# serlcd841.net
KiCad netlist of a schematic drawn in EAGLE
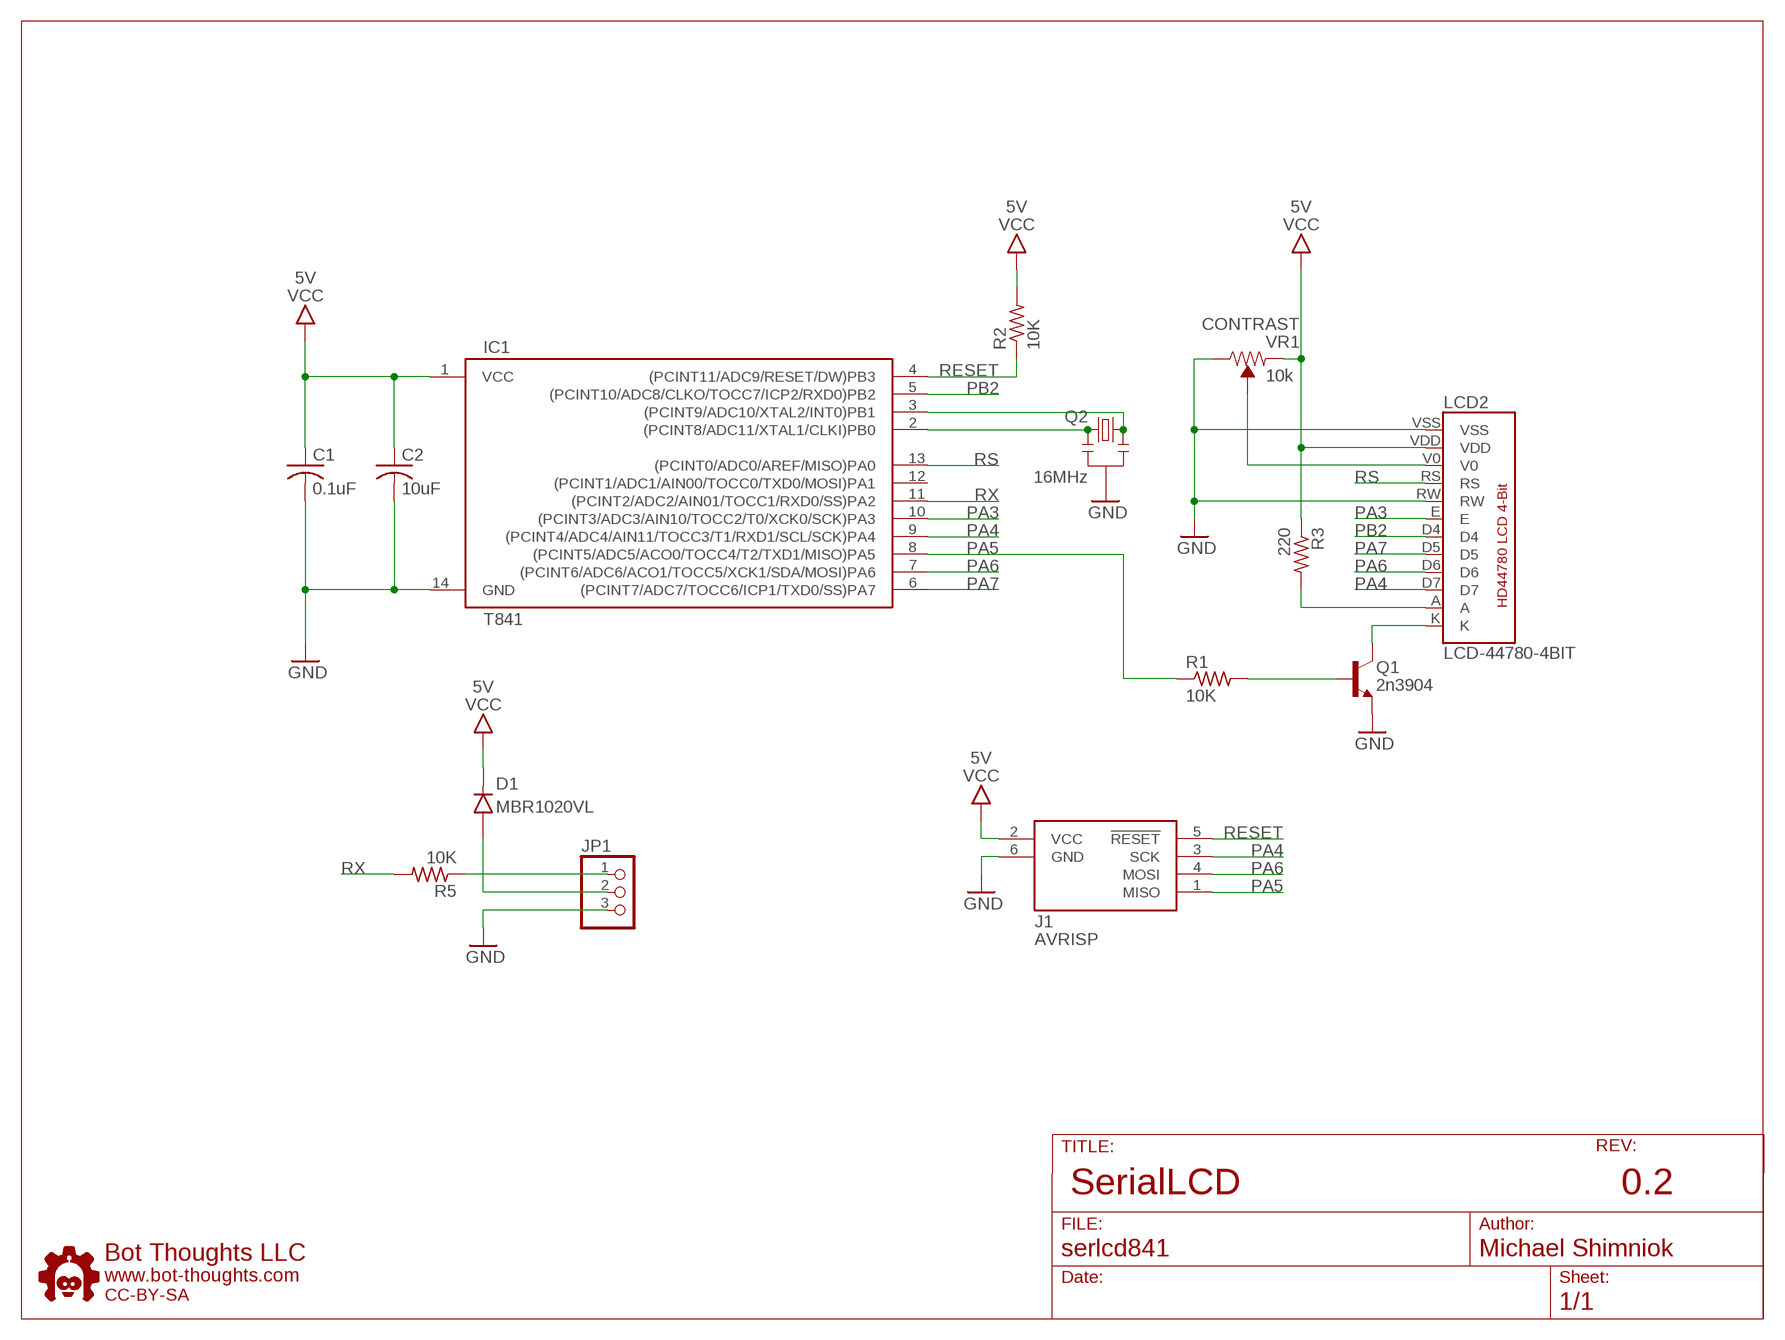
[diagram p0: schematic, sheet 1]

(export (version "E")
  (design (tool "Eeschema 10.0.6"))
  (components
    (comp (ref "C1")
      (value "0.1uF")
      (footprint "eagle-import:0603")
      (libsource (lib "eagle-import") (part "C-0603"))
    )
    (comp (ref "C2")
      (value "10uF")
      (footprint "eagle-import:1206")
      (libsource (lib "eagle-import") (part "C-1206"))
    )
    (comp (ref "D1")
      (value "MBR1020VL")
      (footprint "eagle-import:SOD123FL")
      (libsource (lib "eagle-import") (part "DIODE_SOD123FL"))
    )
    (comp (ref "IC1")
      (value "T841")
      (footprint "eagle-import:SOIC14N")
      (libsource (lib "eagle-import") (part "ATTINY441/841-SSU"))
    )
    (comp (ref "J1")
      (value "AVRISP")
      (footprint "eagle-import:CON6P2R")
      (libsource (lib "eagle-import") (part "AVRISP6_COMPACT"))
    )
    (comp (ref "JP1")
      (value "PINHD-1X03_2.54-S")
      (footprint "eagle-import:1X03-S")
      (libsource (lib "eagle-import") (part "PINHD-1X03_2.54-S"))
    )
    (comp (ref "LCD2")
      (value "LCD-44780-4BIT")
      (footprint "eagle-import:LCD16SIP")
      (libsource (lib "eagle-import") (part "LCD-44780-4BIT"))
    )
    (comp (ref "Q1")
      (value "2n3904")
      (footprint "eagle-import:SOT-23")
      (libsource (lib "eagle-import") (part "BJT-NPNSOT23"))
    )
    (comp (ref "Q2")
      (value "16MHz")
      (footprint "eagle-import:CSTCE_V_C")
      (libsource (lib "eagle-import") (part "RESONATOR_CSTCE_V_C"))
    )
    (comp (ref "R1")
      (value "10K")
      (footprint "eagle-import:0603")
      (libsource (lib "eagle-import") (part "R0603"))
    )
    (comp (ref "R2")
      (value "10K")
      (footprint "eagle-import:0603")
      (libsource (lib "eagle-import") (part "R0603"))
    )
    (comp (ref "R3")
      (value "220")
      (footprint "eagle-import:0603")
      (libsource (lib "eagle-import") (part "R0603"))
    )
    (comp (ref "R5")
      (value "10K")
      (footprint "eagle-import:0603")
      (libsource (lib "eagle-import") (part "R0603"))
    )
    (comp (ref "U$6")
      (value "BTLOGO-LOGO-MD")
      (footprint "eagle-import:BTLOGOM")
      (libsource (lib "eagle-import") (part "BTLOGO-LOGO-MD"))
    )
    (comp (ref "VR1")
      (value "10k")
      (footprint "eagle-import:TRIMPOT-SMD-TC33X")
      (libsource (lib "eagle-import") (part "TRIMPOT-SMD-3MM-OPEN-1/10W-25%"))
    )
  )
  (nets
    (net (code "1") (name "/PA3") (class "Default")
      (node (ref "IC1") (pin "10") (pinfunction "(PCINT3/ADC3/AIN10/TOCC2/T0/XCK0/SCK)PA3_10") (pintype "bidirectional"))
      (node (ref "LCD2") (pin "E") (pinfunction "E_E") (pintype "bidirectional"))
    )
    (net (code "2") (name "/PA4") (class "Default")
      (node (ref "IC1") (pin "9") (pinfunction "(PCINT4/ADC4/AIN11/TOCC3/T1/RXD1/SCL/SCK)PA4_9") (pintype "bidirectional"))
      (node (ref "J1") (pin "3") (pinfunction "SCK_3") (pintype "output"))
      (node (ref "LCD2") (pin "D7") (pinfunction "D7_D7") (pintype "bidirectional"))
    )
    (net (code "3") (name "/PA5") (class "Default")
      (node (ref "IC1") (pin "8") (pinfunction "(PCINT5/ADC5/ACO0/TOCC4/T2/TXD1/MISO)PA5_8") (pintype "bidirectional"))
      (node (ref "J1") (pin "1") (pinfunction "MISO_1") (pintype "input"))
      (node (ref "R1") (pin "1") (pinfunction "1_1") (pintype "passive"))
    )
    (net (code "4") (name "/PA6") (class "Default")
      (node (ref "IC1") (pin "7") (pinfunction "(PCINT6/ADC6/ACO1/TOCC5/XCK1/SDA/MOSI)PA6_7") (pintype "bidirectional"))
      (node (ref "J1") (pin "4") (pinfunction "MOSI_4") (pintype "output"))
      (node (ref "LCD2") (pin "D6") (pinfunction "D6_D6") (pintype "bidirectional"))
    )
    (net (code "5") (name "/PA7") (class "Default")
      (node (ref "IC1") (pin "6") (pinfunction "(PCINT7/ADC7/TOCC6/ICP1/TXD0/SS)PA7_6") (pintype "bidirectional"))
      (node (ref "LCD2") (pin "D5") (pinfunction "D5_D5") (pintype "bidirectional"))
    )
    (net (code "6") (name "/PB2") (class "Default")
      (node (ref "IC1") (pin "5") (pinfunction "(PCINT10/ADC8/CLKO/TOCC7/ICP2/RXD0)PB2_5") (pintype "bidirectional"))
      (node (ref "LCD2") (pin "D4") (pinfunction "D4_D4") (pintype "bidirectional"))
    )
    (net (code "7") (name "/RESET") (class "Default")
      (node (ref "IC1") (pin "4") (pinfunction "(PCINT11/ADC9/RESET/DW)PB3_4") (pintype "bidirectional"))
      (node (ref "J1") (pin "5") (pinfunction "~{RESET}_5") (pintype "output"))
      (node (ref "R2") (pin "1") (pinfunction "1_1") (pintype "passive"))
    )
    (net (code "8") (name "/RS") (class "Default")
      (node (ref "IC1") (pin "13") (pinfunction "(PCINT0/ADC0/AREF/MISO)PA0_13") (pintype "bidirectional"))
      (node (ref "LCD2") (pin "RS") (pinfunction "RS_RS") (pintype "bidirectional"))
    )
    (net (code "9") (name "/RX") (class "Default")
      (node (ref "IC1") (pin "11") (pinfunction "(PCINT2/ADC2/AIN01/TOCC1/RXD0/SS)PA2_11") (pintype "bidirectional"))
      (node (ref "R5") (pin "2") (pinfunction "2_2") (pintype "passive"))
    )
    (net (code "10") (name "5V") (class "Default")
      (node (ref "C1") (pin "1") (pinfunction "+_1") (pintype "passive"))
      (node (ref "C2") (pin "1") (pinfunction "+_1") (pintype "passive"))
      (node (ref "D1") (pin "C") (pinfunction "C_C") (pintype "passive"))
      (node (ref "IC1") (pin "1") (pinfunction "VCC_1") (pintype "bidirectional"))
      (node (ref "J1") (pin "2") (pinfunction "VCC_2") (pintype "power_in"))
      (node (ref "LCD2") (pin "VDD") (pinfunction "VDD_VDD") (pintype "bidirectional"))
      (node (ref "R2") (pin "2") (pinfunction "2_2") (pintype "passive"))
      (node (ref "R3") (pin "1") (pinfunction "1_1") (pintype "passive"))
      (node (ref "VR1") (pin "3") (pinfunction "CCW_3") (pintype "passive"))
    )
    (net (code "11") (name "GND") (class "Default")
      (node (ref "C1") (pin "2") (pinfunction "-_2") (pintype "passive"))
      (node (ref "C2") (pin "2") (pinfunction "-_2") (pintype "passive"))
      (node (ref "IC1") (pin "14") (pinfunction "GND_14") (pintype "bidirectional"))
      (node (ref "J1") (pin "6") (pinfunction "GND_6") (pintype "power_in"))
      (node (ref "JP1") (pin "3") (pinfunction "3_3") (pintype "passive"))
      (node (ref "LCD2") (pin "RW") (pinfunction "RW_RW") (pintype "bidirectional"))
      (node (ref "LCD2") (pin "VSS") (pinfunction "VSS_VSS") (pintype "bidirectional"))
      (node (ref "Q1") (pin "2") (pinfunction "E_2") (pintype "passive"))
      (node (ref "Q2") (pin "GND") (pinfunction "GND_GND") (pintype "passive"))
      (node (ref "VR1") (pin "1") (pinfunction "CW_1") (pintype "passive"))
    )
    (net (code "12") (name "Net-(D1-PadA)") (class "Default")
      (node (ref "D1") (pin "A") (pinfunction "A_A") (pintype "passive"))
      (node (ref "JP1") (pin "2") (pinfunction "2_2") (pintype "passive"))
    )
    (net (code "13") (name "Net-(IC1-(PCINT8{slash}ADC11{slash}XTAL1{slash}CLKI)PB0)") (class "Default")
      (node (ref "IC1") (pin "2") (pinfunction "(PCINT8/ADC11/XTAL1/CLKI)PB0_2") (pintype "bidirectional"))
      (node (ref "Q2") (pin "X2") (pinfunction "X2_X2") (pintype "passive"))
    )
    (net (code "14") (name "Net-(IC1-(PCINT9{slash}ADC10{slash}XTAL2{slash}INT0)PB1)") (class "Default")
      (node (ref "IC1") (pin "3") (pinfunction "(PCINT9/ADC10/XTAL2/INT0)PB1_3") (pintype "bidirectional"))
      (node (ref "Q2") (pin "X1") (pinfunction "X1_X1") (pintype "passive"))
    )
    (net (code "15") (name "Net-(JP1-Pad1)") (class "Default")
      (node (ref "JP1") (pin "1") (pinfunction "1_1") (pintype "passive"))
      (node (ref "R5") (pin "1") (pinfunction "1_1") (pintype "passive"))
    )
    (net (code "16") (name "Net-(LCD2-PadA)") (class "Default")
      (node (ref "LCD2") (pin "A") (pinfunction "A_A") (pintype "bidirectional"))
      (node (ref "R3") (pin "2") (pinfunction "2_2") (pintype "passive"))
    )
    (net (code "17") (name "Net-(Q1-B)") (class "Default")
      (node (ref "Q1") (pin "3") (pinfunction "B_3") (pintype "passive"))
      (node (ref "R1") (pin "2") (pinfunction "2_2") (pintype "passive"))
    )
    (net (code "18") (name "Net-(Q1-C)") (class "Default")
      (node (ref "LCD2") (pin "K") (pinfunction "K_K") (pintype "bidirectional"))
      (node (ref "Q1") (pin "1") (pinfunction "C_1") (pintype "passive"))
    )
    (net (code "19") (name "Net-(VR1-WIPER)") (class "Default")
      (node (ref "LCD2") (pin "V0") (pinfunction "V0_V0") (pintype "bidirectional"))
      (node (ref "VR1") (pin "2") (pinfunction "WIPER_2") (pintype "passive"))
    )
    (net (code "20") (name "unconnected-(IC1-(PCINT1{slash}ADC1{slash}AIN00{slash}TOCC0{slash}TXD0{slash}MOSI)PA1-Pad12)") (class "Default")
      (node (ref "IC1") (pin "12") (pinfunction "(PCINT1/ADC1/AIN00/TOCC0/TXD0/MOSI)PA1_12") (pintype "bidirectional"))
    )
  )
)
